# Keyboard_Scanner_2pp_RevA.net
KiCad netlist of a schematic drawn in EAGLE
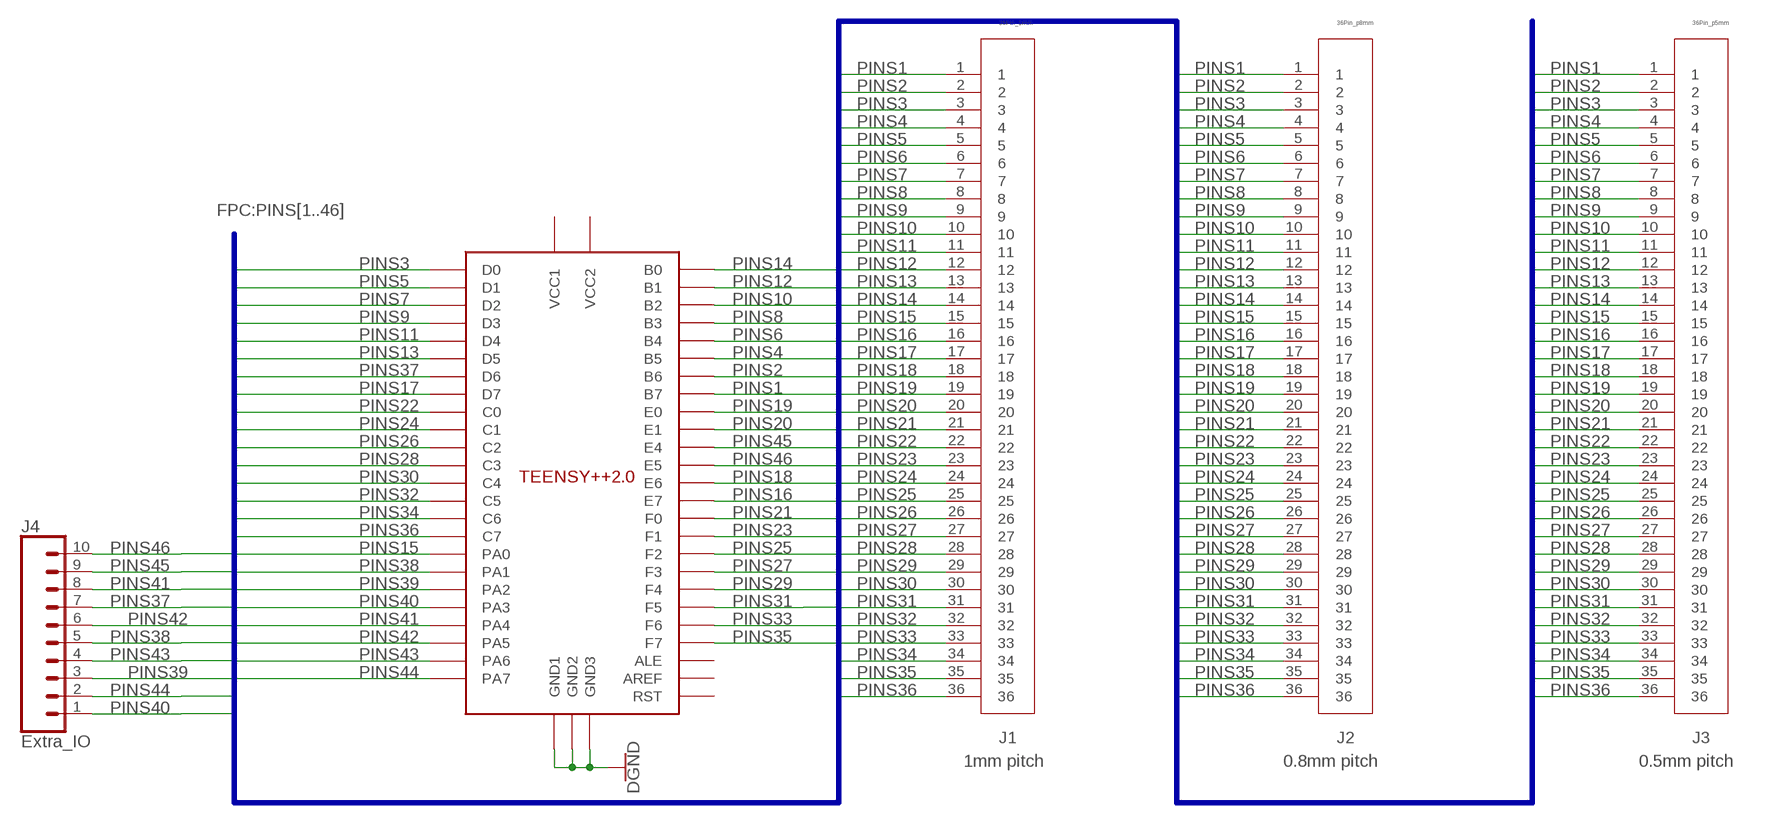
[diagram p0: schematic, sheet 1]

(export (version "E")
  (design (tool "Eeschema 10.0.6"))
  (components
    (comp (ref "J1")
      (value "36Pin_1mm")
      (footprint "eagle-import:FPC36_1MM")
      (libsource (lib "eagle-import") (part "FPC36_1MM"))
    )
    (comp (ref "J2")
      (value "36Pin_p8mm")
      (footprint "eagle-import:FPC36_P8MM")
      (libsource (lib "eagle-import") (part "FPC36_P8MM"))
    )
    (comp (ref "J3")
      (value "36Pin_p5mm")
      (footprint "eagle-import:FPC36_P5MM")
      (libsource (lib "eagle-import") (part "FPC36_P5MM"))
    )
    (comp (ref "J4")
      (value "Extra_IO")
      (footprint "eagle-import:1X10")
      (libsource (lib "eagle-import") (part "CONN_10{dblquote}"))
    )
    (comp (ref "U$1")
      (value "Teensy++2.0")
      (footprint "eagle-import:TEENSYPP2.0")
      (libsource (lib "eagle-import") (part "TEENSYPP2.0"))
    )
  )
  (nets
    (net (code "48") (name "/PINS1") (class "Default")
      (node (ref "J1") (pin "1") (pinfunction "1_1") (pintype "bidirectional"))
      (node (ref "J2") (pin "1") (pinfunction "1_1") (pintype "bidirectional"))
      (node (ref "J3") (pin "1") (pinfunction "1_1") (pintype "bidirectional"))
      (node (ref "U$1") (pin "B7") (pinfunction "B7_B7") (pintype "bidirectional"))
    )
    (net (code "49") (name "/PINS2") (class "Default")
      (node (ref "J1") (pin "2") (pinfunction "2_2") (pintype "bidirectional"))
      (node (ref "J2") (pin "2") (pinfunction "2_2") (pintype "bidirectional"))
      (node (ref "J3") (pin "2") (pinfunction "2_2") (pintype "bidirectional"))
      (node (ref "U$1") (pin "B6") (pinfunction "B6_B6") (pintype "bidirectional"))
    )
    (net (code "50") (name "/PINS3") (class "Default")
      (node (ref "J1") (pin "3") (pinfunction "3_3") (pintype "bidirectional"))
      (node (ref "J2") (pin "3") (pinfunction "3_3") (pintype "bidirectional"))
      (node (ref "J3") (pin "3") (pinfunction "3_3") (pintype "bidirectional"))
      (node (ref "U$1") (pin "D0") (pinfunction "D0_D0") (pintype "bidirectional"))
    )
    (net (code "51") (name "/PINS4") (class "Default")
      (node (ref "J1") (pin "4") (pinfunction "4_4") (pintype "bidirectional"))
      (node (ref "J2") (pin "4") (pinfunction "4_4") (pintype "bidirectional"))
      (node (ref "J3") (pin "4") (pinfunction "4_4") (pintype "bidirectional"))
      (node (ref "U$1") (pin "B5") (pinfunction "B5_B5") (pintype "bidirectional"))
    )
    (net (code "52") (name "/PINS5") (class "Default")
      (node (ref "J1") (pin "5") (pinfunction "5_5") (pintype "bidirectional"))
      (node (ref "J2") (pin "5") (pinfunction "5_5") (pintype "bidirectional"))
      (node (ref "J3") (pin "5") (pinfunction "5_5") (pintype "bidirectional"))
      (node (ref "U$1") (pin "D1") (pinfunction "D1_D1") (pintype "bidirectional"))
    )
    (net (code "53") (name "/PINS6") (class "Default")
      (node (ref "J1") (pin "6") (pinfunction "6_6") (pintype "bidirectional"))
      (node (ref "J2") (pin "6") (pinfunction "6_6") (pintype "bidirectional"))
      (node (ref "J3") (pin "6") (pinfunction "6_6") (pintype "bidirectional"))
      (node (ref "U$1") (pin "B4") (pinfunction "B4_B4") (pintype "bidirectional"))
    )
    (net (code "54") (name "/PINS7") (class "Default")
      (node (ref "J1") (pin "7") (pinfunction "7_7") (pintype "bidirectional"))
      (node (ref "J2") (pin "7") (pinfunction "7_7") (pintype "bidirectional"))
      (node (ref "J3") (pin "7") (pinfunction "7_7") (pintype "bidirectional"))
      (node (ref "U$1") (pin "D2") (pinfunction "D2_D2") (pintype "bidirectional"))
    )
    (net (code "55") (name "/PINS8") (class "Default")
      (node (ref "J1") (pin "8") (pinfunction "8_8") (pintype "bidirectional"))
      (node (ref "J2") (pin "8") (pinfunction "8_8") (pintype "bidirectional"))
      (node (ref "J3") (pin "8") (pinfunction "8_8") (pintype "bidirectional"))
      (node (ref "U$1") (pin "B3") (pinfunction "B3_B3") (pintype "bidirectional"))
    )
    (net (code "56") (name "/PINS9") (class "Default")
      (node (ref "J1") (pin "9") (pinfunction "9_9") (pintype "bidirectional"))
      (node (ref "J2") (pin "9") (pinfunction "9_9") (pintype "bidirectional"))
      (node (ref "J3") (pin "9") (pinfunction "9_9") (pintype "bidirectional"))
      (node (ref "U$1") (pin "D3") (pinfunction "D3_D3") (pintype "bidirectional"))
    )
    (net (code "57") (name "/PINS10") (class "Default")
      (node (ref "J1") (pin "10") (pinfunction "10_10") (pintype "bidirectional"))
      (node (ref "J2") (pin "10") (pinfunction "10_10") (pintype "bidirectional"))
      (node (ref "J3") (pin "10") (pinfunction "10_10") (pintype "bidirectional"))
      (node (ref "U$1") (pin "B2") (pinfunction "B2_B2") (pintype "bidirectional"))
    )
    (net (code "58") (name "/PINS11") (class "Default")
      (node (ref "J1") (pin "11") (pinfunction "11_11") (pintype "bidirectional"))
      (node (ref "J2") (pin "11") (pinfunction "11_11") (pintype "bidirectional"))
      (node (ref "J3") (pin "11") (pinfunction "11_11") (pintype "bidirectional"))
      (node (ref "U$1") (pin "D4") (pinfunction "D4_D4") (pintype "bidirectional"))
    )
    (net (code "59") (name "/PINS12") (class "Default")
      (node (ref "J1") (pin "12") (pinfunction "12_12") (pintype "bidirectional"))
      (node (ref "J2") (pin "12") (pinfunction "12_12") (pintype "bidirectional"))
      (node (ref "J3") (pin "12") (pinfunction "12_12") (pintype "bidirectional"))
      (node (ref "U$1") (pin "B1") (pinfunction "B1_B1") (pintype "bidirectional"))
    )
    (net (code "60") (name "/PINS13") (class "Default")
      (node (ref "J1") (pin "13") (pinfunction "13_13") (pintype "bidirectional"))
      (node (ref "J2") (pin "13") (pinfunction "13_13") (pintype "bidirectional"))
      (node (ref "J3") (pin "13") (pinfunction "13_13") (pintype "bidirectional"))
      (node (ref "U$1") (pin "D5") (pinfunction "D5_D5") (pintype "bidirectional"))
    )
    (net (code "61") (name "/PINS14") (class "Default")
      (node (ref "J1") (pin "14") (pinfunction "14_14") (pintype "bidirectional"))
      (node (ref "J2") (pin "14") (pinfunction "14_14") (pintype "bidirectional"))
      (node (ref "J3") (pin "14") (pinfunction "14_14") (pintype "bidirectional"))
      (node (ref "U$1") (pin "B0") (pinfunction "B0_B0") (pintype "bidirectional"))
    )
    (net (code "62") (name "/PINS15") (class "Default")
      (node (ref "J1") (pin "15") (pinfunction "15_15") (pintype "bidirectional"))
      (node (ref "J2") (pin "15") (pinfunction "15_15") (pintype "bidirectional"))
      (node (ref "J3") (pin "15") (pinfunction "15_15") (pintype "bidirectional"))
      (node (ref "U$1") (pin "PA0") (pinfunction "PA0_PA0") (pintype "bidirectional"))
    )
    (net (code "63") (name "/PINS16") (class "Default")
      (node (ref "J1") (pin "16") (pinfunction "16_16") (pintype "bidirectional"))
      (node (ref "J2") (pin "16") (pinfunction "16_16") (pintype "bidirectional"))
      (node (ref "J3") (pin "16") (pinfunction "16_16") (pintype "bidirectional"))
      (node (ref "U$1") (pin "E7") (pinfunction "E7_E7") (pintype "bidirectional"))
    )
    (net (code "64") (name "/PINS17") (class "Default")
      (node (ref "J1") (pin "17") (pinfunction "17_17") (pintype "bidirectional"))
      (node (ref "J2") (pin "17") (pinfunction "17_17") (pintype "bidirectional"))
      (node (ref "J3") (pin "17") (pinfunction "17_17") (pintype "bidirectional"))
      (node (ref "U$1") (pin "D7") (pinfunction "D7_D7") (pintype "bidirectional"))
    )
    (net (code "65") (name "/PINS18") (class "Default")
      (node (ref "J1") (pin "18") (pinfunction "18_18") (pintype "bidirectional"))
      (node (ref "J2") (pin "18") (pinfunction "18_18") (pintype "bidirectional"))
      (node (ref "J3") (pin "18") (pinfunction "18_18") (pintype "bidirectional"))
      (node (ref "U$1") (pin "E6") (pinfunction "E6_E6") (pintype "bidirectional"))
    )
    (net (code "66") (name "/PINS19") (class "Default")
      (node (ref "J1") (pin "19") (pinfunction "19_19") (pintype "bidirectional"))
      (node (ref "J2") (pin "19") (pinfunction "19_19") (pintype "bidirectional"))
      (node (ref "J3") (pin "19") (pinfunction "19_19") (pintype "bidirectional"))
      (node (ref "U$1") (pin "E0") (pinfunction "E0_E0") (pintype "bidirectional"))
    )
    (net (code "67") (name "/PINS20") (class "Default")
      (node (ref "J1") (pin "20") (pinfunction "20_20") (pintype "bidirectional"))
      (node (ref "J2") (pin "20") (pinfunction "20_20") (pintype "bidirectional"))
      (node (ref "J3") (pin "20") (pinfunction "20_20") (pintype "bidirectional"))
      (node (ref "U$1") (pin "E1") (pinfunction "E1_E1") (pintype "bidirectional"))
    )
    (net (code "68") (name "/PINS21") (class "Default")
      (node (ref "J1") (pin "21") (pinfunction "21_21") (pintype "bidirectional"))
      (node (ref "J2") (pin "21") (pinfunction "21_21") (pintype "bidirectional"))
      (node (ref "J3") (pin "21") (pinfunction "21_21") (pintype "bidirectional"))
      (node (ref "U$1") (pin "F0") (pinfunction "F0_F0") (pintype "bidirectional"))
    )
    (net (code "69") (name "/PINS22") (class "Default")
      (node (ref "J1") (pin "22") (pinfunction "22_22") (pintype "bidirectional"))
      (node (ref "J2") (pin "22") (pinfunction "22_22") (pintype "bidirectional"))
      (node (ref "J3") (pin "22") (pinfunction "22_22") (pintype "bidirectional"))
      (node (ref "U$1") (pin "C0") (pinfunction "C0_C0") (pintype "bidirectional"))
    )
    (net (code "70") (name "/PINS23") (class "Default")
      (node (ref "J1") (pin "23") (pinfunction "23_23") (pintype "bidirectional"))
      (node (ref "J2") (pin "23") (pinfunction "23_23") (pintype "bidirectional"))
      (node (ref "J3") (pin "23") (pinfunction "23_23") (pintype "bidirectional"))
      (node (ref "U$1") (pin "F1") (pinfunction "F1_F1") (pintype "bidirectional"))
    )
    (net (code "71") (name "/PINS24") (class "Default")
      (node (ref "J1") (pin "24") (pinfunction "24_24") (pintype "bidirectional"))
      (node (ref "J2") (pin "24") (pinfunction "24_24") (pintype "bidirectional"))
      (node (ref "J3") (pin "24") (pinfunction "24_24") (pintype "bidirectional"))
      (node (ref "U$1") (pin "C1") (pinfunction "C1_C1") (pintype "bidirectional"))
    )
    (net (code "72") (name "/PINS25") (class "Default")
      (node (ref "J1") (pin "25") (pinfunction "25_25") (pintype "bidirectional"))
      (node (ref "J2") (pin "25") (pinfunction "25_25") (pintype "bidirectional"))
      (node (ref "J3") (pin "25") (pinfunction "25_25") (pintype "bidirectional"))
      (node (ref "U$1") (pin "F2") (pinfunction "F2_F2") (pintype "bidirectional"))
    )
    (net (code "73") (name "/PINS26") (class "Default")
      (node (ref "J1") (pin "26") (pinfunction "26_26") (pintype "bidirectional"))
      (node (ref "J2") (pin "26") (pinfunction "26_26") (pintype "bidirectional"))
      (node (ref "J3") (pin "26") (pinfunction "26_26") (pintype "bidirectional"))
      (node (ref "U$1") (pin "C2") (pinfunction "C2_C2") (pintype "bidirectional"))
    )
    (net (code "74") (name "/PINS27") (class "Default")
      (node (ref "J1") (pin "27") (pinfunction "27_27") (pintype "bidirectional"))
      (node (ref "J2") (pin "27") (pinfunction "27_27") (pintype "bidirectional"))
      (node (ref "J3") (pin "27") (pinfunction "27_27") (pintype "bidirectional"))
      (node (ref "U$1") (pin "F3") (pinfunction "F3_F3") (pintype "bidirectional"))
    )
    (net (code "75") (name "/PINS28") (class "Default")
      (node (ref "J1") (pin "28") (pinfunction "28_28") (pintype "bidirectional"))
      (node (ref "J2") (pin "28") (pinfunction "28_28") (pintype "bidirectional"))
      (node (ref "J3") (pin "28") (pinfunction "28_28") (pintype "bidirectional"))
      (node (ref "U$1") (pin "C3") (pinfunction "C3_C3") (pintype "bidirectional"))
    )
    (net (code "76") (name "/PINS29") (class "Default")
      (node (ref "J1") (pin "29") (pinfunction "29_29") (pintype "bidirectional"))
      (node (ref "J2") (pin "29") (pinfunction "29_29") (pintype "bidirectional"))
      (node (ref "J3") (pin "29") (pinfunction "29_29") (pintype "bidirectional"))
      (node (ref "U$1") (pin "F4") (pinfunction "F4_F4") (pintype "bidirectional"))
    )
    (net (code "77") (name "/PINS30") (class "Default")
      (node (ref "J1") (pin "30") (pinfunction "30_30") (pintype "bidirectional"))
      (node (ref "J2") (pin "30") (pinfunction "30_30") (pintype "bidirectional"))
      (node (ref "J3") (pin "30") (pinfunction "30_30") (pintype "bidirectional"))
      (node (ref "U$1") (pin "C4") (pinfunction "C4_C4") (pintype "bidirectional"))
    )
    (net (code "78") (name "/PINS31") (class "Default")
      (node (ref "J1") (pin "31") (pinfunction "31_31") (pintype "bidirectional"))
      (node (ref "J2") (pin "31") (pinfunction "31_31") (pintype "bidirectional"))
      (node (ref "J3") (pin "31") (pinfunction "31_31") (pintype "bidirectional"))
      (node (ref "U$1") (pin "F5") (pinfunction "F5_F5") (pintype "bidirectional"))
    )
    (net (code "79") (name "/PINS32") (class "Default")
      (node (ref "J1") (pin "32") (pinfunction "32_32") (pintype "bidirectional"))
      (node (ref "J2") (pin "32") (pinfunction "32_32") (pintype "bidirectional"))
      (node (ref "J3") (pin "32") (pinfunction "32_32") (pintype "bidirectional"))
      (node (ref "U$1") (pin "C5") (pinfunction "C5_C5") (pintype "bidirectional"))
    )
    (net (code "80") (name "/PINS33") (class "Default")
      (node (ref "J1") (pin "33") (pinfunction "33_33") (pintype "bidirectional"))
      (node (ref "J2") (pin "33") (pinfunction "33_33") (pintype "bidirectional"))
      (node (ref "J3") (pin "33") (pinfunction "33_33") (pintype "bidirectional"))
      (node (ref "U$1") (pin "F6") (pinfunction "F6_F6") (pintype "bidirectional"))
    )
    (net (code "81") (name "/PINS34") (class "Default")
      (node (ref "J1") (pin "34") (pinfunction "34_34") (pintype "bidirectional"))
      (node (ref "J2") (pin "34") (pinfunction "34_34") (pintype "bidirectional"))
      (node (ref "J3") (pin "34") (pinfunction "34_34") (pintype "bidirectional"))
      (node (ref "U$1") (pin "C6") (pinfunction "C6_C6") (pintype "bidirectional"))
    )
    (net (code "82") (name "/PINS35") (class "Default")
      (node (ref "J1") (pin "35") (pinfunction "35_35") (pintype "bidirectional"))
      (node (ref "J2") (pin "35") (pinfunction "35_35") (pintype "bidirectional"))
      (node (ref "J3") (pin "35") (pinfunction "35_35") (pintype "bidirectional"))
      (node (ref "U$1") (pin "F7") (pinfunction "F7_F7") (pintype "bidirectional"))
    )
    (net (code "83") (name "/PINS36") (class "Default")
      (node (ref "J1") (pin "36") (pinfunction "36_36") (pintype "bidirectional"))
      (node (ref "J2") (pin "36") (pinfunction "36_36") (pintype "bidirectional"))
      (node (ref "J3") (pin "36") (pinfunction "36_36") (pintype "bidirectional"))
      (node (ref "U$1") (pin "C7") (pinfunction "C7_C7") (pintype "bidirectional"))
    )
    (net (code "84") (name "/PINS37") (class "Default")
      (node (ref "J4") (pin "7") (pinfunction "7_7") (pintype "passive"))
      (node (ref "U$1") (pin "D6") (pinfunction "D6_D6") (pintype "bidirectional"))
    )
    (net (code "85") (name "/PINS38") (class "Default")
      (node (ref "J4") (pin "5") (pinfunction "5_5") (pintype "passive"))
      (node (ref "U$1") (pin "PA1") (pinfunction "PA1_PA1") (pintype "bidirectional"))
    )
    (net (code "86") (name "/PINS39") (class "Default")
      (node (ref "J4") (pin "3") (pinfunction "3_3") (pintype "passive"))
      (node (ref "U$1") (pin "PA2") (pinfunction "PA2_PA2") (pintype "bidirectional"))
    )
    (net (code "87") (name "/PINS40") (class "Default")
      (node (ref "J4") (pin "1") (pinfunction "1_1") (pintype "passive"))
      (node (ref "U$1") (pin "PA3") (pinfunction "PA3_PA3") (pintype "bidirectional"))
    )
    (net (code "88") (name "/PINS41") (class "Default")
      (node (ref "J4") (pin "8") (pinfunction "8_8") (pintype "passive"))
      (node (ref "U$1") (pin "PA4") (pinfunction "PA4_PA4") (pintype "bidirectional"))
    )
    (net (code "89") (name "/PINS42") (class "Default")
      (node (ref "J4") (pin "6") (pinfunction "6_6") (pintype "passive"))
      (node (ref "U$1") (pin "PA5") (pinfunction "PA5_PA5") (pintype "bidirectional"))
    )
    (net (code "90") (name "/PINS43") (class "Default")
      (node (ref "J4") (pin "4") (pinfunction "4_4") (pintype "passive"))
      (node (ref "U$1") (pin "PA6") (pinfunction "PA6_PA6") (pintype "bidirectional"))
    )
    (net (code "91") (name "/PINS44") (class "Default")
      (node (ref "J4") (pin "2") (pinfunction "2_2") (pintype "passive"))
      (node (ref "U$1") (pin "PA7") (pinfunction "PA7_PA7") (pintype "bidirectional"))
    )
    (net (code "92") (name "/PINS45") (class "Default")
      (node (ref "J4") (pin "9") (pinfunction "9_9") (pintype "passive"))
      (node (ref "U$1") (pin "E4") (pinfunction "E4_E4") (pintype "bidirectional"))
    )
    (net (code "93") (name "/PINS46") (class "Default")
      (node (ref "J4") (pin "10") (pinfunction "10_10") (pintype "passive"))
      (node (ref "U$1") (pin "E5") (pinfunction "E5_E5") (pintype "bidirectional"))
    )
    (net (code "94") (name "DGND") (class "Default")
      (node (ref "U$1") (pin "GND1") (pinfunction "GND1_GND1") (pintype "bidirectional"))
      (node (ref "U$1") (pin "GND2") (pinfunction "GND2_GND2") (pintype "bidirectional"))
      (node (ref "U$1") (pin "GND3") (pinfunction "GND3_GND3") (pintype "bidirectional"))
    )
    (net (code "95") (name "unconnected-(U$1-PadALE)") (class "Default")
      (node (ref "U$1") (pin "ALE") (pinfunction "ALE_ALE") (pintype "bidirectional"))
    )
    (net (code "96") (name "unconnected-(U$1-PadAREF)") (class "Default")
      (node (ref "U$1") (pin "AREF") (pinfunction "AREF_AREF") (pintype "bidirectional"))
    )
    (net (code "97") (name "unconnected-(U$1-PadRST)") (class "Default")
      (node (ref "U$1") (pin "RST") (pinfunction "RST_RST") (pintype "bidirectional"))
    )
    (net (code "98") (name "unconnected-(U$1-PadVCC1)") (class "Default")
      (node (ref "U$1") (pin "VCC1") (pinfunction "VCC1_VCC1") (pintype "bidirectional"))
    )
    (net (code "99") (name "unconnected-(U$1-PadVCC2)") (class "Default")
      (node (ref "U$1") (pin "VCC2") (pinfunction "VCC2_VCC2") (pintype "bidirectional"))
    )
  )
)
